# Space_Pony_Prototype_3.net
KiCad netlist of a schematic drawn in EasyEDA
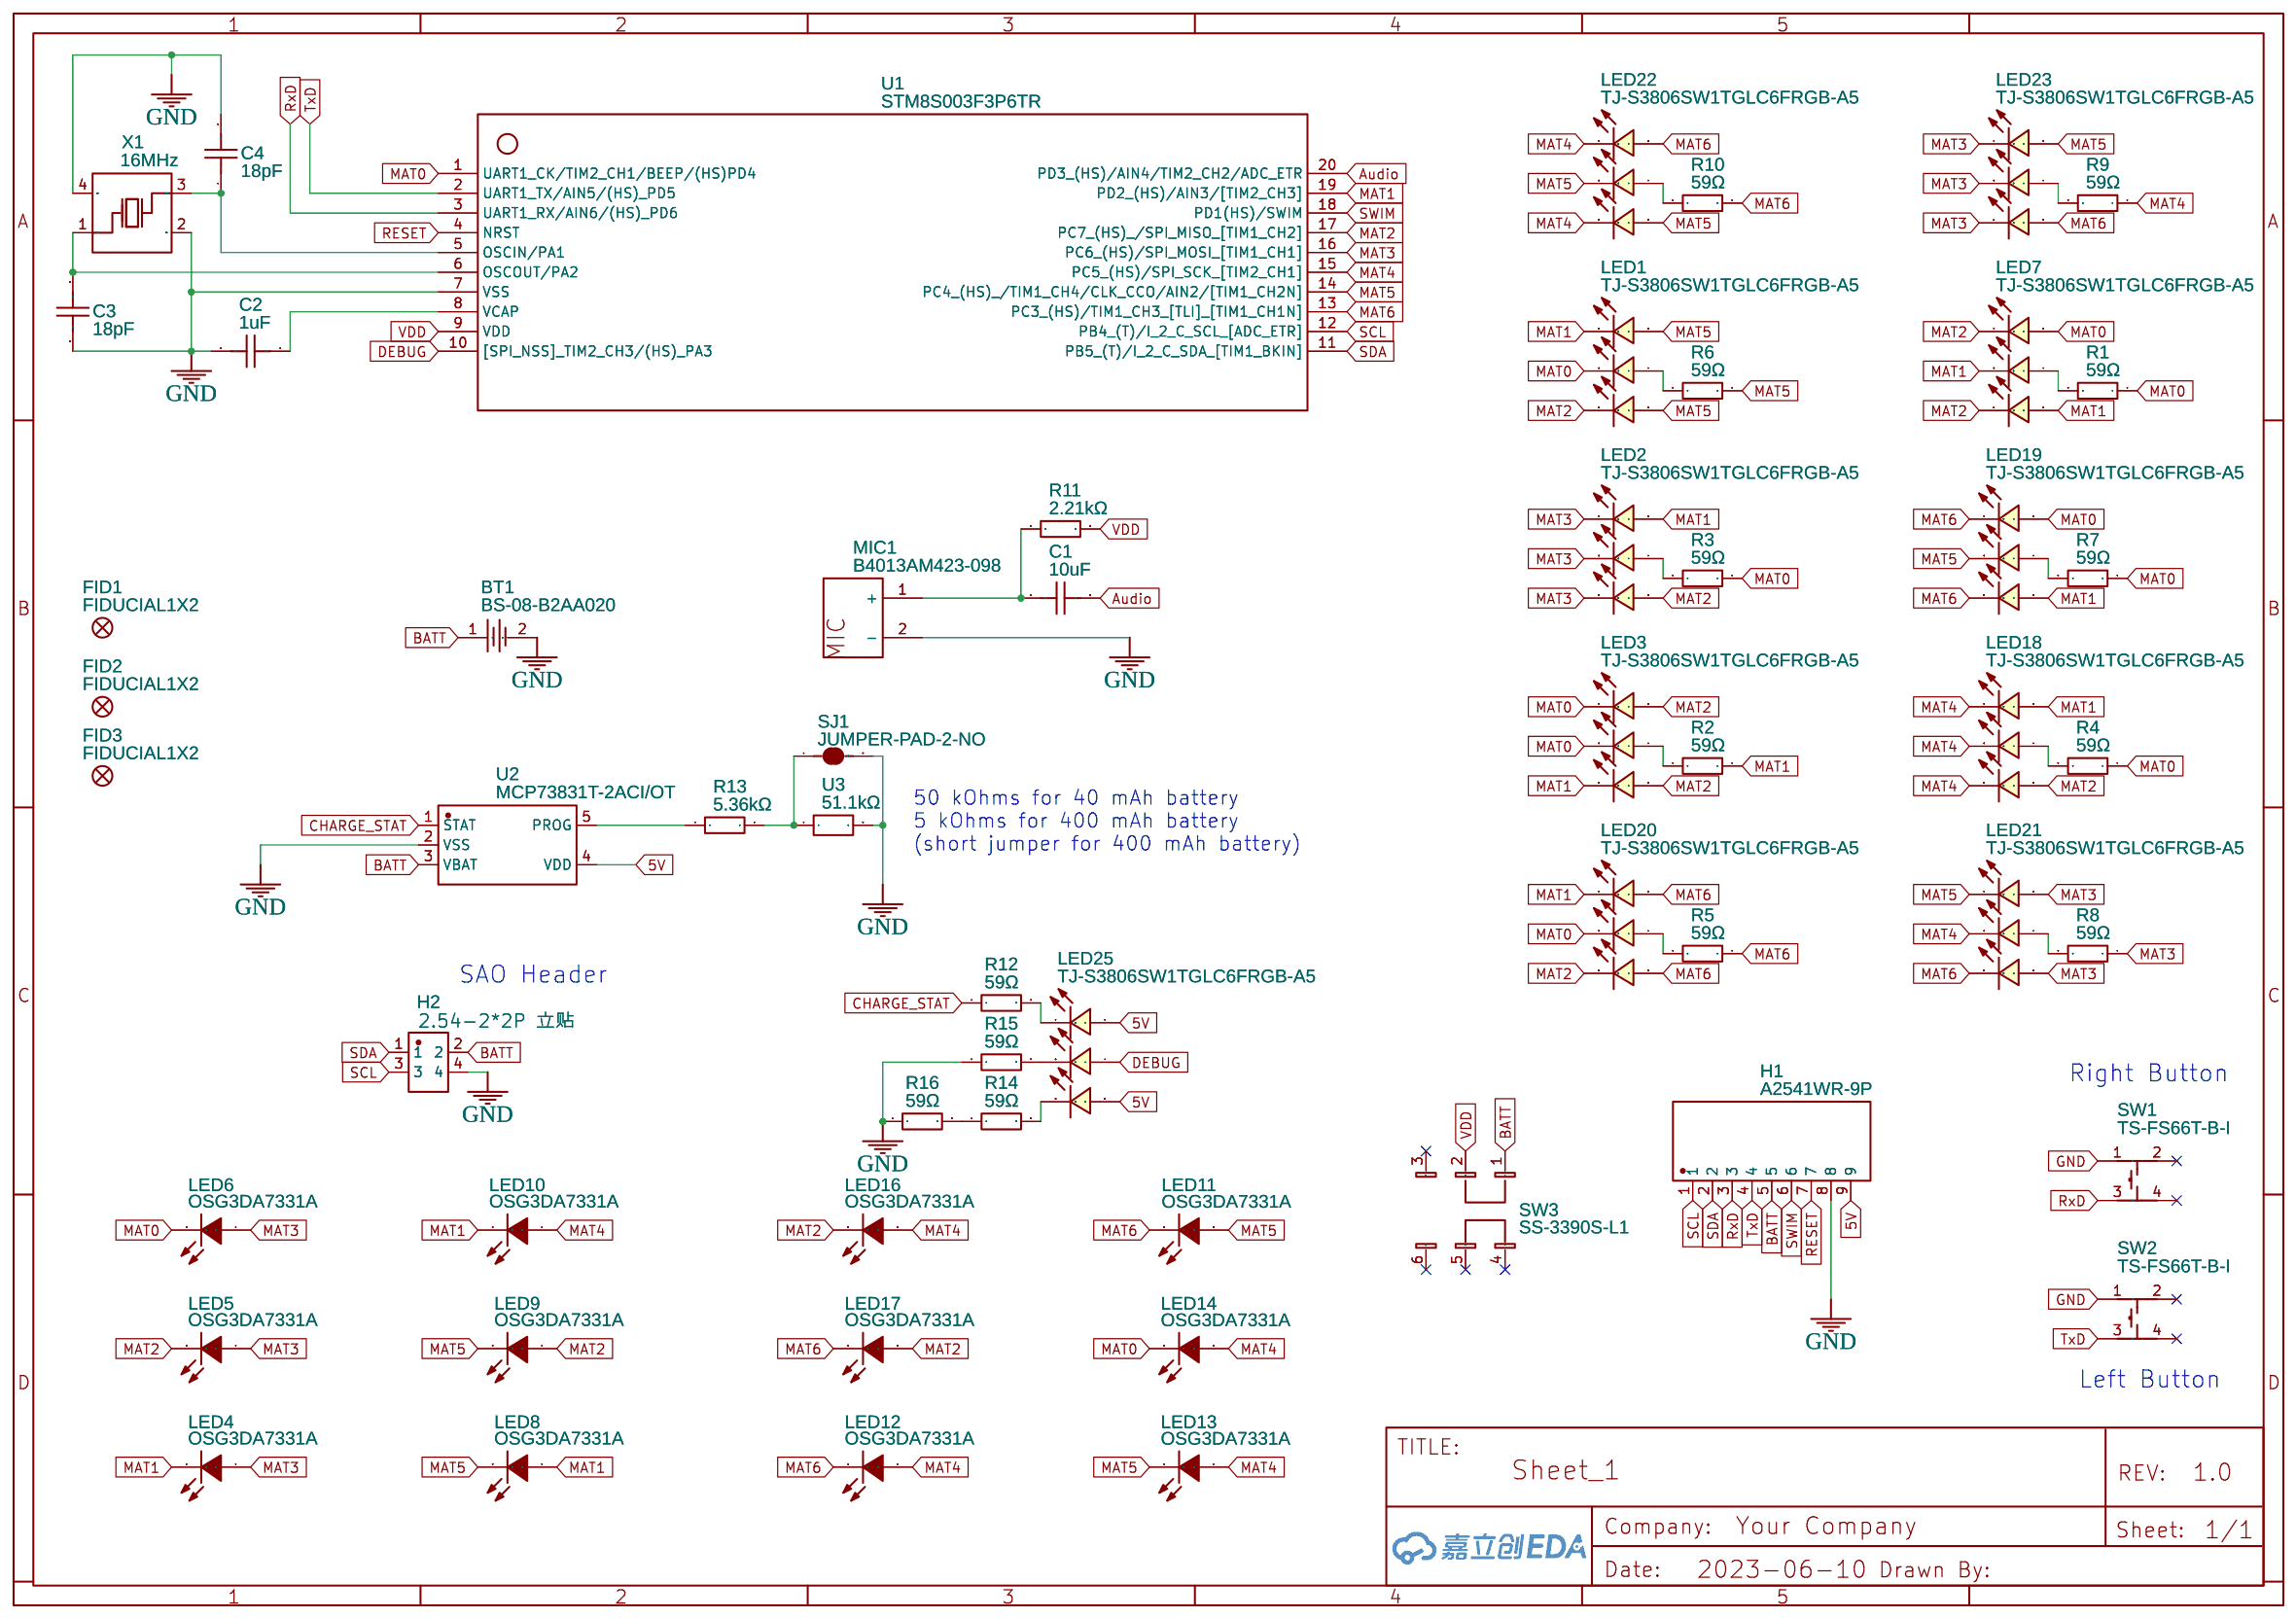
[diagram p0: schematic sheet]

(export (version "E")
  (design (tool "Eeschema 10.0.6"))
  (components
    (comp (ref "BT1")
      (value "BS-08-B2AA020")
      (fields (field (name "BOM_Supplier Part") "C964786"))
      (libsource (lib "") (part "BS-08-B2AA020"))
    )
    (comp (ref "C1")
      (value "10uF")
      (fields
        (field (name "BOM_Manufacturer Part") "GRM155R60J106ME05D")
        (field (name "BOM_Supplier Part") "C723895")
      )
      (libsource (lib "") (part "GRM155R60J106ME05D"))
    )
    (comp (ref "C2")
      (value "1uF")
      (fields
        (field (name "BOM_Manufacturer Part") "CL05B105KQ5NQNC")
        (field (name "BOM_Supplier Part") "C307427")
      )
      (libsource (lib "") (part "CL05B105KQ5NQNC"))
    )
    (comp (ref "C3")
      (value "18pF")
      (fields
        (field (name "BOM_Manufacturer Part") "FN15N180J500PNG")
        (field (name "BOM_Supplier Part") "C363512")
      )
      (libsource (lib "") (part "FN15N180J500PNG"))
    )
    (comp (ref "C4")
      (value "18pF")
      (fields
        (field (name "BOM_Manufacturer Part") "FN15N180J500PNG")
        (field (name "BOM_Supplier Part") "C363512")
      )
      (libsource (lib "") (part "FN15N180J500PNG"))
    )
    (comp (ref "FID1") (value "FIDUCIAL1X2") (libsource (lib "") (part "FIDUCIAL1X2")))
    (comp (ref "FID2") (value "FIDUCIAL1X2") (libsource (lib "") (part "FIDUCIAL1X2")))
    (comp (ref "FID3") (value "FIDUCIAL1X2") (libsource (lib "") (part "FIDUCIAL1X2")))
    (comp (ref "H1")
      (value "A2541WR-9P")
      (fields (field (name "BOM_Supplier Part") "C225495"))
      (libsource (lib "") (part "A2541WR-9P"))
    )
    (comp (ref "H2")
      (value "2.54-2*2P 立贴")
      (fields
        (field (name "BOM_Manufacturer Part") "2.54-2*2P立贴针")
        (field (name "BOM_Supplier Part") "C919361")
      )
      (libsource (lib "") (part "2.54-2*2P 立贴"))
    )
    (comp (ref "LED1")
      (value "TJ-S3806SW1TGLC6FRGB-A5")
      (fields (field (name "BOM_Supplier Part") "C601694"))
      (libsource (lib "") (part "TJ-S3806SW1TGLC6FRGB-A5"))
    )
    (comp (ref "LED2")
      (value "TJ-S3806SW1TGLC6FRGB-A5")
      (fields (field (name "BOM_Supplier Part") "C601694"))
      (libsource (lib "") (part "TJ-S3806SW1TGLC6FRGB-A5"))
    )
    (comp (ref "LED3")
      (value "TJ-S3806SW1TGLC6FRGB-A5")
      (fields (field (name "BOM_Supplier Part") "C601694"))
      (libsource (lib "") (part "TJ-S3806SW1TGLC6FRGB-A5"))
    )
    (comp (ref "LED4")
      (value "OSG3DA7331A")
      (fields (field (name "BOM_Supplier Part") "C268274"))
      (libsource (lib "") (part "OSG3DA7331A"))
    )
    (comp (ref "LED5")
      (value "OSG3DA7331A")
      (fields (field (name "BOM_Supplier Part") "C268274"))
      (libsource (lib "") (part "OSG3DA7331A"))
    )
    (comp (ref "LED6")
      (value "OSG3DA7331A")
      (fields (field (name "BOM_Supplier Part") "C268274"))
      (libsource (lib "") (part "OSG3DA7331A"))
    )
    (comp (ref "LED7")
      (value "TJ-S3806SW1TGLC6FRGB-A5")
      (fields (field (name "BOM_Supplier Part") "C601694"))
      (libsource (lib "") (part "TJ-S3806SW1TGLC6FRGB-A5"))
    )
    (comp (ref "LED8")
      (value "OSG3DA7331A")
      (fields (field (name "BOM_Supplier Part") "C268274"))
      (libsource (lib "") (part "OSG3DA7331A"))
    )
    (comp (ref "LED9")
      (value "OSG3DA7331A")
      (fields (field (name "BOM_Supplier Part") "C268274"))
      (libsource (lib "") (part "OSG3DA7331A"))
    )
    (comp (ref "LED10")
      (value "OSG3DA7331A")
      (fields (field (name "BOM_Supplier Part") "C268274"))
      (libsource (lib "") (part "OSG3DA7331A"))
    )
    (comp (ref "LED11")
      (value "OSG3DA7331A")
      (fields (field (name "BOM_Supplier Part") "C268274"))
      (libsource (lib "") (part "OSG3DA7331A"))
    )
    (comp (ref "LED12")
      (value "OSG3DA7331A")
      (fields (field (name "BOM_Supplier Part") "C268274"))
      (libsource (lib "") (part "OSG3DA7331A"))
    )
    (comp (ref "LED13")
      (value "OSG3DA7331A")
      (fields (field (name "BOM_Supplier Part") "C268274"))
      (libsource (lib "") (part "OSG3DA7331A"))
    )
    (comp (ref "LED14")
      (value "OSG3DA7331A")
      (fields (field (name "BOM_Supplier Part") "C268274"))
      (libsource (lib "") (part "OSG3DA7331A"))
    )
    (comp (ref "LED16")
      (value "OSG3DA7331A")
      (fields (field (name "BOM_Supplier Part") "C268274"))
      (libsource (lib "") (part "OSG3DA7331A"))
    )
    (comp (ref "LED17")
      (value "OSG3DA7331A")
      (fields (field (name "BOM_Supplier Part") "C268274"))
      (libsource (lib "") (part "OSG3DA7331A"))
    )
    (comp (ref "LED18")
      (value "TJ-S3806SW1TGLC6FRGB-A5")
      (fields (field (name "BOM_Supplier Part") "C601694"))
      (libsource (lib "") (part "TJ-S3806SW1TGLC6FRGB-A5"))
    )
    (comp (ref "LED19")
      (value "TJ-S3806SW1TGLC6FRGB-A5")
      (fields (field (name "BOM_Supplier Part") "C601694"))
      (libsource (lib "") (part "TJ-S3806SW1TGLC6FRGB-A5"))
    )
    (comp (ref "LED20")
      (value "TJ-S3806SW1TGLC6FRGB-A5")
      (fields (field (name "BOM_Supplier Part") "C601694"))
      (libsource (lib "") (part "TJ-S3806SW1TGLC6FRGB-A5"))
    )
    (comp (ref "LED21")
      (value "TJ-S3806SW1TGLC6FRGB-A5")
      (fields (field (name "BOM_Supplier Part") "C601694"))
      (libsource (lib "") (part "TJ-S3806SW1TGLC6FRGB-A5"))
    )
    (comp (ref "LED22")
      (value "TJ-S3806SW1TGLC6FRGB-A5")
      (fields (field (name "BOM_Supplier Part") "C601694"))
      (libsource (lib "") (part "TJ-S3806SW1TGLC6FRGB-A5"))
    )
    (comp (ref "LED23")
      (value "TJ-S3806SW1TGLC6FRGB-A5")
      (fields (field (name "BOM_Supplier Part") "C601694"))
      (libsource (lib "") (part "TJ-S3806SW1TGLC6FRGB-A5"))
    )
    (comp (ref "LED25")
      (value "TJ-S3806SW1TGLC6FRGB-A5")
      (fields (field (name "BOM_Supplier Part") "C601694"))
      (libsource (lib "") (part "TJ-S3806SW1TGLC6FRGB-A5"))
    )
    (comp (ref "MIC1")
      (value "B4013AM423-098")
      (fields (field (name "BOM_Supplier Part") "C2835889"))
      (libsource (lib "") (part "B4013AM423-098"))
    )
    (comp (ref "R1")
      (value "59Ω")
      (fields
        (field (name "BOM_Manufacturer Part") "RTT0259R0FTH")
        (field (name "BOM_Supplier Part") "C159005")
      )
      (libsource (lib "") (part "RTT0259R0FTH_1"))
    )
    (comp (ref "R2")
      (value "59Ω")
      (fields
        (field (name "BOM_Manufacturer Part") "RTT0259R0FTH")
        (field (name "BOM_Supplier Part") "C159005")
      )
      (libsource (lib "") (part "RTT0259R0FTH_1"))
    )
    (comp (ref "R3")
      (value "59Ω")
      (fields
        (field (name "BOM_Manufacturer Part") "RTT0259R0FTH")
        (field (name "BOM_Supplier Part") "C159005")
      )
      (libsource (lib "") (part "RTT0259R0FTH_1"))
    )
    (comp (ref "R4")
      (value "59Ω")
      (fields
        (field (name "BOM_Manufacturer Part") "RTT0259R0FTH")
        (field (name "BOM_Supplier Part") "C159005")
      )
      (libsource (lib "") (part "RTT0259R0FTH_1"))
    )
    (comp (ref "R5")
      (value "59Ω")
      (fields
        (field (name "BOM_Manufacturer Part") "RTT0259R0FTH")
        (field (name "BOM_Supplier Part") "C159005")
      )
      (libsource (lib "") (part "RTT0259R0FTH_1"))
    )
    (comp (ref "R6")
      (value "59Ω")
      (fields
        (field (name "BOM_Manufacturer Part") "RTT0259R0FTH")
        (field (name "BOM_Supplier Part") "C159005")
      )
      (libsource (lib "") (part "RTT0259R0FTH_1"))
    )
    (comp (ref "R7")
      (value "59Ω")
      (fields
        (field (name "BOM_Manufacturer Part") "RTT0259R0FTH")
        (field (name "BOM_Supplier Part") "C159005")
      )
      (libsource (lib "") (part "RTT0259R0FTH_1"))
    )
    (comp (ref "R8")
      (value "59Ω")
      (fields
        (field (name "BOM_Manufacturer Part") "RTT0259R0FTH")
        (field (name "BOM_Supplier Part") "C159005")
      )
      (libsource (lib "") (part "RTT0259R0FTH_1"))
    )
    (comp (ref "R9")
      (value "59Ω")
      (fields
        (field (name "BOM_Manufacturer Part") "RTT0259R0FTH")
        (field (name "BOM_Supplier Part") "C159005")
      )
      (libsource (lib "") (part "RTT0259R0FTH_1"))
    )
    (comp (ref "R10")
      (value "59Ω")
      (fields
        (field (name "BOM_Manufacturer Part") "RTT0259R0FTH")
        (field (name "BOM_Supplier Part") "C159005")
      )
      (libsource (lib "") (part "RTT0259R0FTH_1"))
    )
    (comp (ref "R11")
      (value "2.21kΩ")
      (fields
        (field (name "BOM_Manufacturer Part") "CR0402FF2211G")
        (field (name "BOM_Supplier Part") "C100313")
      )
      (libsource (lib "") (part "CR0402FF2211G"))
    )
    (comp (ref "R12")
      (value "59Ω")
      (fields
        (field (name "BOM_Manufacturer Part") "RTT0259R0FTH")
        (field (name "BOM_Supplier Part") "C159005")
      )
      (libsource (lib "") (part "RTT0259R0FTH"))
    )
    (comp (ref "R13")
      (value "5.36kΩ")
      (fields
        (field (name "BOM_Manufacturer Part") "CR0402FF5361G")
        (field (name "BOM_Supplier Part") "C100471")
      )
      (libsource (lib "") (part "CR0402FF5361G"))
    )
    (comp (ref "R14")
      (value "59Ω")
      (fields
        (field (name "BOM_Manufacturer Part") "RTT0259R0FTH")
        (field (name "BOM_Supplier Part") "C159005")
      )
      (libsource (lib "") (part "RTT0259R0FTH"))
    )
    (comp (ref "R15")
      (value "59Ω")
      (fields
        (field (name "BOM_Manufacturer Part") "RTT0259R0FTH")
        (field (name "BOM_Supplier Part") "C159005")
      )
      (libsource (lib "") (part "RTT0259R0FTH"))
    )
    (comp (ref "R16")
      (value "59Ω")
      (fields
        (field (name "BOM_Manufacturer Part") "RTT0259R0FTH")
        (field (name "BOM_Supplier Part") "C159005")
      )
      (libsource (lib "") (part "RTT0259R0FTH"))
    )
    (comp (ref "SJ1") (value "JUMPER-PAD-2-NO") (libsource (lib "") (part "JUMPER-PAD-2-NO")))
    (comp (ref "SW1")
      (value "TS-FS66T-B-I")
      (fields (field (name "BOM_Supplier Part") "C500114"))
      (libsource (lib "") (part "TS-FS66T-B-I"))
    )
    (comp (ref "SW2")
      (value "TS-FS66T-B-I")
      (fields (field (name "BOM_Supplier Part") "C500114"))
      (libsource (lib "") (part "TS-FS66T-B-I"))
    )
    (comp (ref "SW3")
      (value "SS-3390S-L1")
      (fields (field (name "BOM_Supplier Part") "C318998"))
      (libsource (lib "") (part "SS-3390S-L1"))
    )
    (comp (ref "U1")
      (value "STM8S003F3P6TR")
      (fields (field (name "BOM_Supplier Part") "C52717"))
      (libsource (lib "") (part "STM8S003F3P6TR"))
    )
    (comp (ref "U2")
      (value "MCP73831T-2ACI/OT")
      (fields (field (name "BOM_Supplier Part") "C424093"))
      (libsource (lib "") (part "MCP73831T-2ACI/OT"))
    )
    (comp (ref "U3")
      (value "51.1kΩ")
      (fields
        (field (name "BOM_Manufacturer Part") "MCR01MZPF5112")
        (field (name "BOM_Supplier Part") "C509676")
      )
      (libsource (lib "") (part "MCR01MZPF5112"))
    )
    (comp (ref "X1")
      (value "16MHz")
      (fields
        (field (name "BOM_Manufacturer Part") "7V16000001")
        (field (name "BOM_Supplier Part") "C331581")
      )
      (libsource (lib "") (part "7V16000001"))
    )
  )
  (nets
    (net (code "1") (name "5V") (class "Default")
      (node (ref "H1") (pin "9") (pinfunction "9_9") (pintype "unspecified"))
      (node (ref "LED25") (pin "2") (pinfunction "A_2") (pintype "unspecified"))
      (node (ref "LED25") (pin "6") (pinfunction "A_6") (pintype "unspecified"))
      (node (ref "U2") (pin "4") (pinfunction "VDD_4") (pintype "unspecified"))
    )
    (net (code "2") (name "Audio") (class "Default")
      (node (ref "C1") (pin "2") (pinfunction "2_2") (pintype "unspecified"))
      (node (ref "U1") (pin "20") (pinfunction "PD3_(HS)/AIN4/TIM2_CH2/ADC_ETR_20") (pintype "unspecified"))
    )
    (net (code "3") (name "BATT") (class "Default")
      (node (ref "BT1") (pin "1") (pinfunction "1_1") (pintype "input"))
      (node (ref "H1") (pin "5") (pinfunction "5_5") (pintype "unspecified"))
      (node (ref "H2") (pin "2") (pinfunction "2_2") (pintype "unspecified"))
      (node (ref "SW3") (pin "1") (pinfunction "1_1") (pintype "unspecified"))
      (node (ref "U2") (pin "3") (pinfunction "VBAT_3") (pintype "unspecified"))
    )
    (net (code "4") (name "CHARGE_STAT") (class "Default")
      (node (ref "R12") (pin "1") (pinfunction "1_1") (pintype "unspecified"))
      (node (ref "U2") (pin "1") (pinfunction "STAT_1") (pintype "unspecified"))
    )
    (net (code "5") (name "DEBUG") (class "Default")
      (node (ref "LED25") (pin "4") (pinfunction "A_4") (pintype "unspecified"))
      (node (ref "U1") (pin "10") (pinfunction "[SPI_NSS]_TIM2_CH3/(HS)_PA3_10") (pintype "unspecified"))
    )
    (net (code "6") (name "GND") (class "Default")
      (node (ref "BT1") (pin "2") (pinfunction "2_2") (pintype "input"))
      (node (ref "C2") (pin "2") (pinfunction "2_2") (pintype "unspecified"))
      (node (ref "C3") (pin "1") (pinfunction "1_1") (pintype "unspecified"))
      (node (ref "C4") (pin "2") (pinfunction "2_2") (pintype "unspecified"))
      (node (ref "H1") (pin "8") (pinfunction "8_8") (pintype "unspecified"))
      (node (ref "H2") (pin "4") (pinfunction "4_4") (pintype "unspecified"))
      (node (ref "MIC1") (pin "2") (pinfunction "-_2") (pintype "unspecified"))
      (node (ref "R15") (pin "1") (pinfunction "1_1") (pintype "unspecified"))
      (node (ref "R16") (pin "1") (pinfunction "1_1") (pintype "unspecified"))
      (node (ref "SJ1") (pin "2") (pinfunction "2_2") (pintype "unspecified"))
      (node (ref "SW1") (pin "1") (pinfunction "1_1") (pintype "unspecified"))
      (node (ref "SW2") (pin "1") (pinfunction "1_1") (pintype "unspecified"))
      (node (ref "U1") (pin "7") (pinfunction "VSS_7") (pintype "unspecified"))
      (node (ref "U2") (pin "2") (pinfunction "VSS_2") (pintype "unspecified"))
      (node (ref "U3") (pin "2") (pinfunction "2_2") (pintype "unspecified"))
      (node (ref "X1") (pin "2") (pinfunction "GND_2") (pintype "input"))
      (node (ref "X1") (pin "4") (pinfunction "GND_4") (pintype "input"))
    )
    (net (code "7") (name "MAT0") (class "Default")
      (node (ref "LED1") (pin "3") (pinfunction "C_3") (pintype "unspecified"))
      (node (ref "LED14") (pin "2") (pinfunction "K_2") (pintype "unspecified"))
      (node (ref "LED19") (pin "2") (pinfunction "A_2") (pintype "unspecified"))
      (node (ref "LED20") (pin "3") (pinfunction "C_3") (pintype "unspecified"))
      (node (ref "LED3") (pin "1") (pinfunction "C_1") (pintype "unspecified"))
      (node (ref "LED3") (pin "3") (pinfunction "C_3") (pintype "unspecified"))
      (node (ref "LED6") (pin "2") (pinfunction "K_2") (pintype "unspecified"))
      (node (ref "LED7") (pin "2") (pinfunction "A_2") (pintype "unspecified"))
      (node (ref "R1") (pin "1") (pinfunction "1_1") (pintype "unspecified"))
      (node (ref "R3") (pin "1") (pinfunction "1_1") (pintype "unspecified"))
      (node (ref "R4") (pin "1") (pinfunction "1_1") (pintype "unspecified"))
      (node (ref "R7") (pin "1") (pinfunction "1_1") (pintype "unspecified"))
      (node (ref "U1") (pin "1") (pinfunction "UART1_CK/TIM2_CH1/BEEP/(HS)PD4_1") (pintype "unspecified"))
    )
    (net (code "8") (name "MAT1") (class "Default")
      (node (ref "LED1") (pin "1") (pinfunction "C_1") (pintype "unspecified"))
      (node (ref "LED10") (pin "2") (pinfunction "K_2") (pintype "unspecified"))
      (node (ref "LED18") (pin "2") (pinfunction "A_2") (pintype "unspecified"))
      (node (ref "LED19") (pin "6") (pinfunction "A_6") (pintype "unspecified"))
      (node (ref "LED2") (pin "2") (pinfunction "A_2") (pintype "unspecified"))
      (node (ref "LED20") (pin "1") (pinfunction "C_1") (pintype "unspecified"))
      (node (ref "LED3") (pin "5") (pinfunction "C_5") (pintype "unspecified"))
      (node (ref "LED4") (pin "2") (pinfunction "K_2") (pintype "unspecified"))
      (node (ref "LED7") (pin "3") (pinfunction "C_3") (pintype "unspecified"))
      (node (ref "LED7") (pin "6") (pinfunction "A_6") (pintype "unspecified"))
      (node (ref "LED8") (pin "1") (pinfunction "A_1") (pintype "unspecified"))
      (node (ref "R2") (pin "1") (pinfunction "1_1") (pintype "unspecified"))
      (node (ref "U1") (pin "19") (pinfunction "PD2_(HS)/AIN3/[TIM2_CH3]_19") (pintype "unspecified"))
    )
    (net (code "9") (name "MAT2") (class "Default")
      (node (ref "LED1") (pin "5") (pinfunction "C_5") (pintype "unspecified"))
      (node (ref "LED16") (pin "2") (pinfunction "K_2") (pintype "unspecified"))
      (node (ref "LED17") (pin "1") (pinfunction "A_1") (pintype "unspecified"))
      (node (ref "LED18") (pin "6") (pinfunction "A_6") (pintype "unspecified"))
      (node (ref "LED2") (pin "6") (pinfunction "A_6") (pintype "unspecified"))
      (node (ref "LED20") (pin "5") (pinfunction "C_5") (pintype "unspecified"))
      (node (ref "LED3") (pin "2") (pinfunction "A_2") (pintype "unspecified"))
      (node (ref "LED3") (pin "6") (pinfunction "A_6") (pintype "unspecified"))
      (node (ref "LED5") (pin "2") (pinfunction "K_2") (pintype "unspecified"))
      (node (ref "LED7") (pin "1") (pinfunction "C_1") (pintype "unspecified"))
      (node (ref "LED7") (pin "5") (pinfunction "C_5") (pintype "unspecified"))
      (node (ref "LED9") (pin "1") (pinfunction "A_1") (pintype "unspecified"))
      (node (ref "U1") (pin "17") (pinfunction "PC7_(HS)_/SPI_MISO_[TIM1_CH2]_17") (pintype "unspecified"))
    )
    (net (code "10") (name "MAT3") (class "Default")
      (node (ref "LED2") (pin "1") (pinfunction "C_1") (pintype "unspecified"))
      (node (ref "LED2") (pin "3") (pinfunction "C_3") (pintype "unspecified"))
      (node (ref "LED2") (pin "5") (pinfunction "C_5") (pintype "unspecified"))
      (node (ref "LED21") (pin "2") (pinfunction "A_2") (pintype "unspecified"))
      (node (ref "LED21") (pin "6") (pinfunction "A_6") (pintype "unspecified"))
      (node (ref "LED23") (pin "1") (pinfunction "C_1") (pintype "unspecified"))
      (node (ref "LED23") (pin "3") (pinfunction "C_3") (pintype "unspecified"))
      (node (ref "LED23") (pin "5") (pinfunction "C_5") (pintype "unspecified"))
      (node (ref "LED4") (pin "1") (pinfunction "A_1") (pintype "unspecified"))
      (node (ref "LED5") (pin "1") (pinfunction "A_1") (pintype "unspecified"))
      (node (ref "LED6") (pin "1") (pinfunction "A_1") (pintype "unspecified"))
      (node (ref "R8") (pin "1") (pinfunction "1_1") (pintype "unspecified"))
      (node (ref "U1") (pin "16") (pinfunction "PC6_(HS)/SPI_MOSI_[TIM1_CH1]_16") (pintype "unspecified"))
    )
    (net (code "11") (name "MAT4") (class "Default")
      (node (ref "LED10") (pin "1") (pinfunction "A_1") (pintype "unspecified"))
      (node (ref "LED12") (pin "1") (pinfunction "A_1") (pintype "unspecified"))
      (node (ref "LED13") (pin "1") (pinfunction "A_1") (pintype "unspecified"))
      (node (ref "LED14") (pin "1") (pinfunction "A_1") (pintype "unspecified"))
      (node (ref "LED16") (pin "1") (pinfunction "A_1") (pintype "unspecified"))
      (node (ref "LED18") (pin "1") (pinfunction "C_1") (pintype "unspecified"))
      (node (ref "LED18") (pin "3") (pinfunction "C_3") (pintype "unspecified"))
      (node (ref "LED18") (pin "5") (pinfunction "C_5") (pintype "unspecified"))
      (node (ref "LED21") (pin "3") (pinfunction "C_3") (pintype "unspecified"))
      (node (ref "LED22") (pin "1") (pinfunction "C_1") (pintype "unspecified"))
      (node (ref "LED22") (pin "5") (pinfunction "C_5") (pintype "unspecified"))
      (node (ref "R9") (pin "1") (pinfunction "1_1") (pintype "unspecified"))
      (node (ref "U1") (pin "15") (pinfunction "PC5_(HS)/SPI_SCK_[TIM2_CH1]_15") (pintype "unspecified"))
    )
    (net (code "12") (name "MAT5") (class "Default")
      (node (ref "LED1") (pin "2") (pinfunction "A_2") (pintype "unspecified"))
      (node (ref "LED1") (pin "6") (pinfunction "A_6") (pintype "unspecified"))
      (node (ref "LED11") (pin "1") (pinfunction "A_1") (pintype "unspecified"))
      (node (ref "LED13") (pin "2") (pinfunction "K_2") (pintype "unspecified"))
      (node (ref "LED19") (pin "3") (pinfunction "C_3") (pintype "unspecified"))
      (node (ref "LED21") (pin "1") (pinfunction "C_1") (pintype "unspecified"))
      (node (ref "LED22") (pin "3") (pinfunction "C_3") (pintype "unspecified"))
      (node (ref "LED22") (pin "6") (pinfunction "A_6") (pintype "unspecified"))
      (node (ref "LED23") (pin "2") (pinfunction "A_2") (pintype "unspecified"))
      (node (ref "LED8") (pin "2") (pinfunction "K_2") (pintype "unspecified"))
      (node (ref "LED9") (pin "2") (pinfunction "K_2") (pintype "unspecified"))
      (node (ref "R6") (pin "1") (pinfunction "1_1") (pintype "unspecified"))
      (node (ref "U1") (pin "14") (pinfunction "PC4_(HS)_/TIM1_CH4/CLK_CCO/AIN2/[TIM1_CH2N]_14") (pintype "unspecified"))
    )
    (net (code "13") (name "MAT6") (class "Default")
      (node (ref "LED11") (pin "2") (pinfunction "K_2") (pintype "unspecified"))
      (node (ref "LED12") (pin "2") (pinfunction "K_2") (pintype "unspecified"))
      (node (ref "LED17") (pin "2") (pinfunction "K_2") (pintype "unspecified"))
      (node (ref "LED19") (pin "1") (pinfunction "C_1") (pintype "unspecified"))
      (node (ref "LED19") (pin "5") (pinfunction "C_5") (pintype "unspecified"))
      (node (ref "LED20") (pin "2") (pinfunction "A_2") (pintype "unspecified"))
      (node (ref "LED20") (pin "6") (pinfunction "A_6") (pintype "unspecified"))
      (node (ref "LED21") (pin "5") (pinfunction "C_5") (pintype "unspecified"))
      (node (ref "LED22") (pin "2") (pinfunction "A_2") (pintype "unspecified"))
      (node (ref "LED23") (pin "6") (pinfunction "A_6") (pintype "unspecified"))
      (node (ref "R10") (pin "1") (pinfunction "1_1") (pintype "unspecified"))
      (node (ref "R5") (pin "1") (pinfunction "1_1") (pintype "unspecified"))
      (node (ref "U1") (pin "13") (pinfunction "PC3_(HS)/TIM1_CH3_[TLI]_[TIM1_CH1N]_13") (pintype "unspecified"))
    )
    (net (code "14") (name "Net-(LED1-A-Pad4)") (class "Default")
      (node (ref "LED1") (pin "4") (pinfunction "A_4") (pintype "unspecified"))
      (node (ref "R6") (pin "2") (pinfunction "2_2") (pintype "unspecified"))
    )
    (net (code "15") (name "Net-(LED2-A-Pad4)") (class "Default")
      (node (ref "LED2") (pin "4") (pinfunction "A_4") (pintype "unspecified"))
      (node (ref "R3") (pin "2") (pinfunction "2_2") (pintype "unspecified"))
    )
    (net (code "16") (name "Net-(LED3-A-Pad4)") (class "Default")
      (node (ref "LED3") (pin "4") (pinfunction "A_4") (pintype "unspecified"))
      (node (ref "R2") (pin "2") (pinfunction "2_2") (pintype "unspecified"))
    )
    (net (code "17") (name "Net-(LED7-A-Pad4)") (class "Default")
      (node (ref "LED7") (pin "4") (pinfunction "A_4") (pintype "unspecified"))
      (node (ref "R1") (pin "2") (pinfunction "2_2") (pintype "unspecified"))
    )
    (net (code "18") (name "Net-(LED18-A-Pad4)") (class "Default")
      (node (ref "LED18") (pin "4") (pinfunction "A_4") (pintype "unspecified"))
      (node (ref "R4") (pin "2") (pinfunction "2_2") (pintype "unspecified"))
    )
    (net (code "19") (name "Net-(LED19-A-Pad4)") (class "Default")
      (node (ref "LED19") (pin "4") (pinfunction "A_4") (pintype "unspecified"))
      (node (ref "R7") (pin "2") (pinfunction "2_2") (pintype "unspecified"))
    )
    (net (code "20") (name "Net-(LED20-A-Pad4)") (class "Default")
      (node (ref "LED20") (pin "4") (pinfunction "A_4") (pintype "unspecified"))
      (node (ref "R5") (pin "2") (pinfunction "2_2") (pintype "unspecified"))
    )
    (net (code "21") (name "Net-(LED21-A-Pad4)") (class "Default")
      (node (ref "LED21") (pin "4") (pinfunction "A_4") (pintype "unspecified"))
      (node (ref "R8") (pin "2") (pinfunction "2_2") (pintype "unspecified"))
    )
    (net (code "22") (name "Net-(LED22-A-Pad4)") (class "Default")
      (node (ref "LED22") (pin "4") (pinfunction "A_4") (pintype "unspecified"))
      (node (ref "R10") (pin "2") (pinfunction "2_2") (pintype "unspecified"))
    )
    (net (code "23") (name "Net-(LED23-A-Pad4)") (class "Default")
      (node (ref "LED23") (pin "4") (pinfunction "A_4") (pintype "unspecified"))
      (node (ref "R9") (pin "2") (pinfunction "2_2") (pintype "unspecified"))
    )
    (net (code "24") (name "Net-(LED25-C-Pad1)") (class "Default")
      (node (ref "LED25") (pin "1") (pinfunction "C_1") (pintype "unspecified"))
      (node (ref "R12") (pin "2") (pinfunction "2_2") (pintype "unspecified"))
    )
    (net (code "25") (name "Net-(LED25-C-Pad3)") (class "Default")
      (node (ref "LED25") (pin "3") (pinfunction "C_3") (pintype "unspecified"))
      (node (ref "R15") (pin "2") (pinfunction "2_2") (pintype "unspecified"))
    )
    (net (code "26") (name "Net-(LED25-C-Pad5)") (class "Default")
      (node (ref "LED25") (pin "5") (pinfunction "C_5") (pintype "unspecified"))
      (node (ref "R14") (pin "2") (pinfunction "2_2") (pintype "unspecified"))
    )
    (net (code "27") (name "Net-(MIC1-+)") (class "Default")
      (node (ref "C1") (pin "1") (pinfunction "1_1") (pintype "unspecified"))
      (node (ref "MIC1") (pin "1") (pinfunction "+_1") (pintype "unspecified"))
      (node (ref "R11") (pin "1") (pinfunction "1_1") (pintype "input"))
    )
    (net (code "28") (name "Net-(R13-Pad2)") (class "Default")
      (node (ref "R13") (pin "2") (pinfunction "2_2") (pintype "input"))
      (node (ref "SJ1") (pin "1") (pinfunction "1_1") (pintype "unspecified"))
      (node (ref "U3") (pin "1") (pinfunction "1_1") (pintype "unspecified"))
    )
    (net (code "29") (name "Net-(R14-Pad1)") (class "Default")
      (node (ref "R14") (pin "1") (pinfunction "1_1") (pintype "unspecified"))
      (node (ref "R16") (pin "2") (pinfunction "2_2") (pintype "unspecified"))
    )
    (net (code "30") (name "Net-(U1-OSCIN{slash}PA1)") (class "Default")
      (node (ref "C4") (pin "1") (pinfunction "1_1") (pintype "unspecified"))
      (node (ref "U1") (pin "5") (pinfunction "OSCIN/PA1_5") (pintype "unspecified"))
      (node (ref "X1") (pin "3") (pinfunction "OSC2_3") (pintype "input"))
    )
    (net (code "31") (name "Net-(U1-OSCOUT{slash}PA2)") (class "Default")
      (node (ref "C3") (pin "2") (pinfunction "2_2") (pintype "unspecified"))
      (node (ref "U1") (pin "6") (pinfunction "OSCOUT/PA2_6") (pintype "unspecified"))
      (node (ref "X1") (pin "1") (pinfunction "OSC1_1") (pintype "input"))
    )
    (net (code "32") (name "Net-(U1-VCAP)") (class "Default")
      (node (ref "C2") (pin "1") (pinfunction "1_1") (pintype "unspecified"))
      (node (ref "U1") (pin "8") (pinfunction "VCAP_8") (pintype "unspecified"))
    )
    (net (code "33") (name "Net-(U2-PROG)") (class "Default")
      (node (ref "R13") (pin "1") (pinfunction "1_1") (pintype "input"))
      (node (ref "U2") (pin "5") (pinfunction "PROG_5") (pintype "unspecified"))
    )
    (net (code "34") (name "RESET") (class "Default")
      (node (ref "H1") (pin "7") (pinfunction "7_7") (pintype "unspecified"))
      (node (ref "U1") (pin "4") (pinfunction "NRST_4") (pintype "unspecified"))
    )
    (net (code "35") (name "RxD") (class "Default")
      (node (ref "H1") (pin "3") (pinfunction "3_3") (pintype "unspecified"))
      (node (ref "SW1") (pin "3") (pinfunction "3_3") (pintype "unspecified"))
      (node (ref "U1") (pin "3") (pinfunction "UART1_RX/AIN6/(HS)_PD6_3") (pintype "unspecified"))
    )
    (net (code "36") (name "SCL") (class "Default")
      (node (ref "H1") (pin "1") (pinfunction "1_1") (pintype "unspecified"))
      (node (ref "H2") (pin "3") (pinfunction "3_3") (pintype "unspecified"))
      (node (ref "U1") (pin "12") (pinfunction "PB4_(T)/I_2_C_SCL_[ADC_ETR]_12") (pintype "unspecified"))
    )
    (net (code "37") (name "SDA") (class "Default")
      (node (ref "H1") (pin "2") (pinfunction "2_2") (pintype "unspecified"))
      (node (ref "H2") (pin "1") (pinfunction "1_1") (pintype "unspecified"))
      (node (ref "U1") (pin "11") (pinfunction "PB5_(T)/I_2_C_SDA_[TIM1_BKIN]_11") (pintype "unspecified"))
    )
    (net (code "38") (name "SWIM") (class "Default")
      (node (ref "H1") (pin "6") (pinfunction "6_6") (pintype "unspecified"))
      (node (ref "U1") (pin "18") (pinfunction "PD1(HS)/SWIM_18") (pintype "unspecified"))
    )
    (net (code "39") (name "TxD") (class "Default")
      (node (ref "H1") (pin "4") (pinfunction "4_4") (pintype "unspecified"))
      (node (ref "SW2") (pin "3") (pinfunction "3_3") (pintype "unspecified"))
      (node (ref "U1") (pin "2") (pinfunction "UART1_TX/AIN5/(HS)_PD5_2") (pintype "unspecified"))
    )
    (net (code "40") (name "VDD") (class "Default")
      (node (ref "R11") (pin "2") (pinfunction "2_2") (pintype "input"))
      (node (ref "SW3") (pin "2") (pinfunction "2_2") (pintype "unspecified"))
      (node (ref "U1") (pin "9") (pinfunction "VDD_9") (pintype "unspecified"))
    )
    (net (code "41") (name "unconnected-(SW1-Pad2)") (class "Default")
      (node (ref "SW1") (pin "2") (pinfunction "2_2") (pintype "unspecified+no_connect"))
    )
    (net (code "42") (name "unconnected-(SW1-Pad4)") (class "Default")
      (node (ref "SW1") (pin "4") (pinfunction "4_4") (pintype "unspecified+no_connect"))
    )
    (net (code "43") (name "unconnected-(SW2-Pad2)") (class "Default")
      (node (ref "SW2") (pin "2") (pinfunction "2_2") (pintype "unspecified+no_connect"))
    )
    (net (code "44") (name "unconnected-(SW2-Pad4)") (class "Default")
      (node (ref "SW2") (pin "4") (pinfunction "4_4") (pintype "unspecified+no_connect"))
    )
    (net (code "45") (name "unconnected-(SW3-Pad3)") (class "Default")
      (node (ref "SW3") (pin "3") (pinfunction "3_3") (pintype "unspecified+no_connect"))
    )
    (net (code "46") (name "unconnected-(SW3-Pad4)") (class "Default")
      (node (ref "SW3") (pin "4") (pinfunction "4_4") (pintype "unspecified+no_connect"))
    )
    (net (code "47") (name "unconnected-(SW3-Pad5)") (class "Default")
      (node (ref "SW3") (pin "5") (pinfunction "5_5") (pintype "unspecified+no_connect"))
    )
    (net (code "48") (name "unconnected-(SW3-Pad6)") (class "Default")
      (node (ref "SW3") (pin "6") (pinfunction "6_6") (pintype "unspecified+no_connect"))
    )
  )
)
